# lortinchen.net
KiCad netlist of a schematic drawn in EAGLE
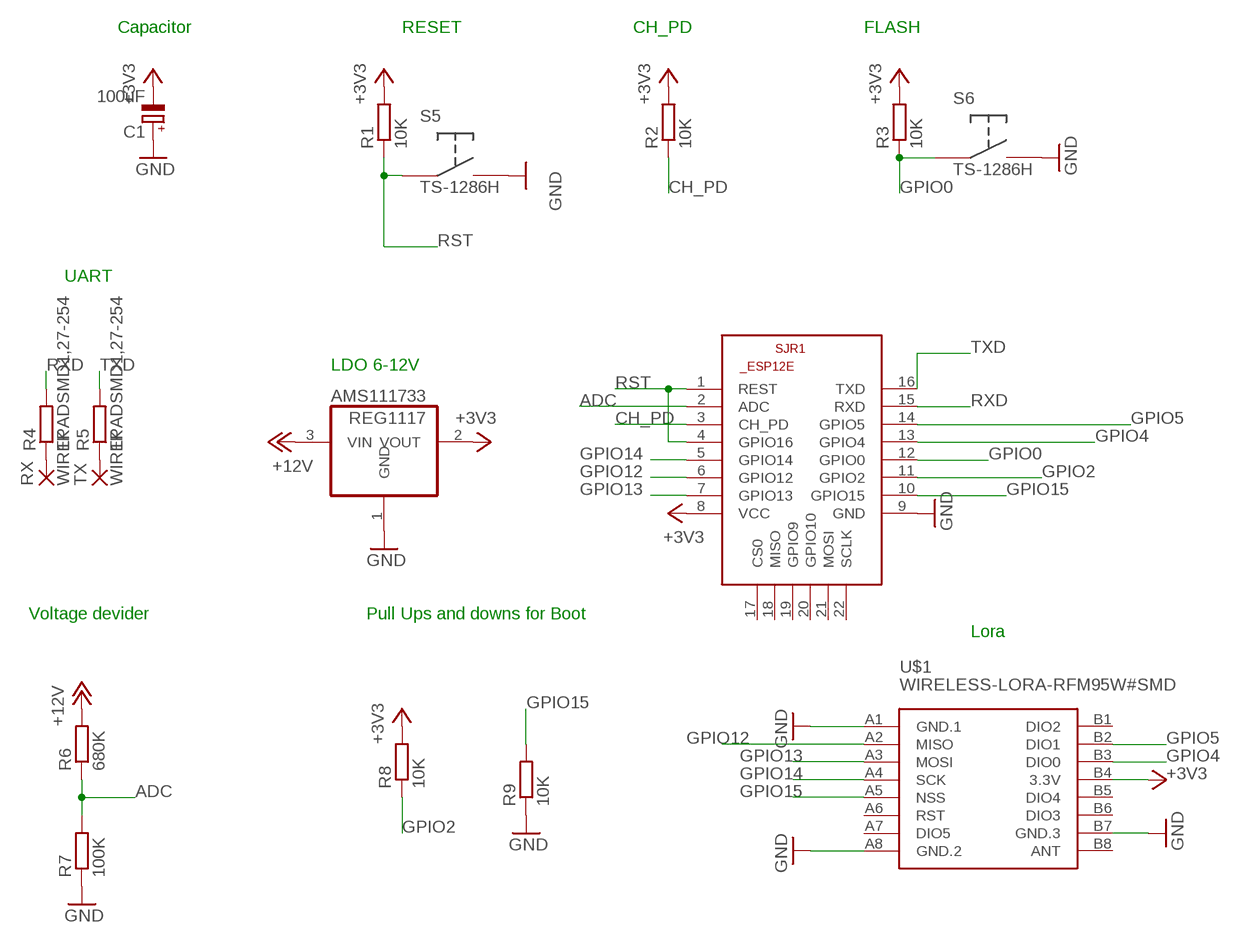
[diagram p0: schematic, sheet 1]

(export (version "E")
  (design (tool "Eeschema 10.0.6"))
  (components
    (comp (ref "AMS111733")
      (value "REG1117")
      (footprint "eagle-import:SOT223")
      (libsource (lib "eagle-import") (part "REG1117"))
    )
    (comp (ref "C1")
      (value "100uF")
      (footprint "eagle-import:C_6032-28R")
      (libsource (lib "eagle-import") (part "CPOL-EUC/6032-28R"))
    )
    (comp (ref "R1")
      (value "10K")
      (footprint "eagle-import:R0603")
      (libsource (lib "eagle-import") (part "R-EU_R0603"))
    )
    (comp (ref "R2")
      (value "10K")
      (footprint "eagle-import:R0603")
      (libsource (lib "eagle-import") (part "R-EU_R0603"))
    )
    (comp (ref "R3")
      (value "10K")
      (footprint "eagle-import:R0603")
      (libsource (lib "eagle-import") (part "R-EU_R0603"))
    )
    (comp (ref "R4")
      (value "1K")
      (footprint "eagle-import:R0603")
      (libsource (lib "eagle-import") (part "R-EU_R0603"))
    )
    (comp (ref "R5")
      (value "1K")
      (footprint "eagle-import:R0603")
      (libsource (lib "eagle-import") (part "R-EU_R0603"))
    )
    (comp (ref "R6")
      (value "680K")
      (footprint "eagle-import:R0603")
      (libsource (lib "eagle-import") (part "R-EU_R0603"))
    )
    (comp (ref "R7")
      (value "100K")
      (footprint "eagle-import:R0603")
      (libsource (lib "eagle-import") (part "R-EU_R0603"))
    )
    (comp (ref "R8")
      (value "10K")
      (footprint "eagle-import:R0603")
      (libsource (lib "eagle-import") (part "R-EU_R0603"))
    )
    (comp (ref "R9")
      (value "10K")
      (footprint "eagle-import:R0603")
      (libsource (lib "eagle-import") (part "R-EU_R0603"))
    )
    (comp (ref "RX")
      (value "WIREPADSMD1,27-254")
      (footprint "eagle-import:SMD1,27-2,54")
      (libsource (lib "eagle-import") (part "WIREPADSMD1,27-254"))
    )
    (comp (ref "S5")
      (value "TS-1286H")
      (footprint "eagle-import:TS-1268H")
      (libsource (lib "eagle-import") (part "TS-1286H"))
    )
    (comp (ref "S6")
      (value "TS-1286H")
      (footprint "eagle-import:TS-1268H")
      (libsource (lib "eagle-import") (part "TS-1286H"))
    )
    (comp (ref "SJR1")
      (value "ESP8266-12EESP12E")
      (footprint "eagle-import:ESP8266-ESP12E")
      (libsource (lib "eagle-import") (part "ESP8266-12EESP12E"))
    )
    (comp (ref "TX")
      (value "WIREPADSMD1,27-254")
      (footprint "eagle-import:SMD1,27-2,54")
      (libsource (lib "eagle-import") (part "WIREPADSMD1,27-254"))
    )
    (comp (ref "U$1")
      (value "WIRELESS-LORA-RFM95W#SMD")
      (footprint "eagle-import:WIRELESS-LORA-RFM95W#SMD")
      (libsource (lib "eagle-import") (part "WIRELESS-LORA-RFM95W#SMD"))
    )
  )
  (nets
    (net (code "1") (name "+3V3") (class "Default")
      (node (ref "AMS111733") (pin "2") (pinfunction "VOUT_2") (pintype "output"))
      (node (ref "C1") (pin "-") (pinfunction "-_-") (pintype "passive"))
      (node (ref "R1") (pin "2") (pinfunction "2_2") (pintype "passive"))
      (node (ref "R2") (pin "2") (pinfunction "2_2") (pintype "passive"))
      (node (ref "R3") (pin "2") (pinfunction "2_2") (pintype "passive"))
      (node (ref "R8") (pin "2") (pinfunction "2_2") (pintype "passive"))
      (node (ref "SJR1") (pin "8") (pinfunction "VCC_8") (pintype "bidirectional"))
      (node (ref "U$1") (pin "B4") (pinfunction "3.3V_B4") (pintype "power_in"))
    )
    (net (code "2") (name "+12V") (class "Default")
      (node (ref "AMS111733") (pin "3") (pinfunction "VIN_3") (pintype "input"))
      (node (ref "R6") (pin "2") (pinfunction "2_2") (pintype "passive"))
    )
    (net (code "3") (name "/ADC") (class "Default")
      (node (ref "R6") (pin "1") (pinfunction "1_1") (pintype "passive"))
      (node (ref "R7") (pin "2") (pinfunction "2_2") (pintype "passive"))
      (node (ref "SJR1") (pin "2") (pinfunction "ADC_2") (pintype "bidirectional"))
    )
    (net (code "4") (name "/CH_PD") (class "Default")
      (node (ref "R2") (pin "1") (pinfunction "1_1") (pintype "passive"))
      (node (ref "SJR1") (pin "3") (pinfunction "CH_PD_3") (pintype "bidirectional"))
    )
    (net (code "5") (name "/GPIO0") (class "Default")
      (node (ref "R3") (pin "1") (pinfunction "1_1") (pintype "passive"))
      (node (ref "S6") (pin "P$1") (pinfunction "P$1_P$1") (pintype "bidirectional"))
      (node (ref "SJR1") (pin "12") (pinfunction "GPIO0_12") (pintype "bidirectional"))
    )
    (net (code "6") (name "/GPIO2") (class "Default")
      (node (ref "R8") (pin "1") (pinfunction "1_1") (pintype "passive"))
      (node (ref "SJR1") (pin "11") (pinfunction "GPIO2_11") (pintype "bidirectional"))
    )
    (net (code "7") (name "/GPIO4") (class "Default")
      (node (ref "SJR1") (pin "13") (pinfunction "GPIO4_13") (pintype "bidirectional"))
      (node (ref "U$1") (pin "B3") (pinfunction "DIO0_B3") (pintype "bidirectional"))
    )
    (net (code "8") (name "/GPIO5") (class "Default")
      (node (ref "SJR1") (pin "14") (pinfunction "GPIO5_14") (pintype "bidirectional"))
      (node (ref "U$1") (pin "B2") (pinfunction "DIO1_B2") (pintype "bidirectional"))
    )
    (net (code "9") (name "/GPIO12") (class "Default")
      (node (ref "SJR1") (pin "6") (pinfunction "GPIO12_6") (pintype "bidirectional"))
      (node (ref "U$1") (pin "A2") (pinfunction "MISO_A2") (pintype "bidirectional"))
    )
    (net (code "10") (name "/GPIO13") (class "Default")
      (node (ref "SJR1") (pin "7") (pinfunction "GPIO13_7") (pintype "bidirectional"))
      (node (ref "U$1") (pin "A3") (pinfunction "MOSI_A3") (pintype "bidirectional"))
    )
    (net (code "11") (name "/GPIO14") (class "Default")
      (node (ref "SJR1") (pin "5") (pinfunction "GPIO14_5") (pintype "bidirectional"))
      (node (ref "U$1") (pin "A4") (pinfunction "SCK_A4") (pintype "bidirectional"))
    )
    (net (code "12") (name "/GPIO15") (class "Default")
      (node (ref "R9") (pin "2") (pinfunction "2_2") (pintype "passive"))
      (node (ref "SJR1") (pin "10") (pinfunction "GPIO15_10") (pintype "bidirectional"))
      (node (ref "U$1") (pin "A5") (pinfunction "NSS_A5") (pintype "bidirectional"))
    )
    (net (code "13") (name "/RST") (class "Default")
      (node (ref "R1") (pin "1") (pinfunction "1_1") (pintype "passive"))
      (node (ref "S5") (pin "P$1") (pinfunction "P$1_P$1") (pintype "bidirectional"))
      (node (ref "SJR1") (pin "1") (pinfunction "REST_1") (pintype "bidirectional"))
      (node (ref "SJR1") (pin "4") (pinfunction "GPIO16_4") (pintype "bidirectional"))
    )
    (net (code "14") (name "/RXD") (class "Default")
      (node (ref "R4") (pin "2") (pinfunction "2_2") (pintype "passive"))
      (node (ref "SJR1") (pin "15") (pinfunction "RXD_15") (pintype "bidirectional"))
    )
    (net (code "15") (name "/TXD") (class "Default")
      (node (ref "R5") (pin "2") (pinfunction "2_2") (pintype "passive"))
      (node (ref "SJR1") (pin "16") (pinfunction "TXD_16") (pintype "bidirectional"))
    )
    (net (code "16") (name "GND") (class "Default")
      (node (ref "AMS111733") (pin "1") (pinfunction "GND_1") (pintype "power_in"))
      (node (ref "C1") (pin "+") (pinfunction "+_+") (pintype "passive"))
      (node (ref "R7") (pin "1") (pinfunction "1_1") (pintype "passive"))
      (node (ref "R9") (pin "1") (pinfunction "1_1") (pintype "passive"))
      (node (ref "S5") (pin "P$2") (pinfunction "P$2_P$2") (pintype "bidirectional"))
      (node (ref "S6") (pin "P$2") (pinfunction "P$2_P$2") (pintype "bidirectional"))
      (node (ref "SJR1") (pin "9") (pinfunction "GND_9") (pintype "bidirectional"))
      (node (ref "U$1") (pin "A1") (pinfunction "GND.1_A1") (pintype "power_in"))
      (node (ref "U$1") (pin "A8") (pinfunction "GND.2_A8") (pintype "power_in"))
      (node (ref "U$1") (pin "B7") (pinfunction "GND.3_B7") (pintype "power_in"))
    )
    (net (code "17") (name "Net-(RX-P)") (class "Default")
      (node (ref "R4") (pin "1") (pinfunction "1_1") (pintype "passive"))
      (node (ref "RX") (pin "1") (pinfunction "P_1") (pintype "passive"))
    )
    (net (code "18") (name "Net-(TX-P)") (class "Default")
      (node (ref "R5") (pin "1") (pinfunction "1_1") (pintype "passive"))
      (node (ref "TX") (pin "1") (pinfunction "P_1") (pintype "passive"))
    )
    (net (code "19") (name "unconnected-(SJR1-CS0-Pad17)") (class "Default")
      (node (ref "SJR1") (pin "17") (pinfunction "CS0_17") (pintype "bidirectional"))
    )
    (net (code "20") (name "unconnected-(SJR1-GPIO9-Pad19)") (class "Default")
      (node (ref "SJR1") (pin "19") (pinfunction "GPIO9_19") (pintype "bidirectional"))
    )
    (net (code "21") (name "unconnected-(SJR1-GPIO10-Pad20)") (class "Default")
      (node (ref "SJR1") (pin "20") (pinfunction "GPIO10_20") (pintype "bidirectional"))
    )
    (net (code "22") (name "unconnected-(SJR1-MISO-Pad18)") (class "Default")
      (node (ref "SJR1") (pin "18") (pinfunction "MISO_18") (pintype "bidirectional"))
    )
    (net (code "23") (name "unconnected-(SJR1-MOSI-Pad21)") (class "Default")
      (node (ref "SJR1") (pin "21") (pinfunction "MOSI_21") (pintype "bidirectional"))
    )
    (net (code "24") (name "unconnected-(SJR1-SCLK-Pad22)") (class "Default")
      (node (ref "SJR1") (pin "22") (pinfunction "SCLK_22") (pintype "bidirectional"))
    )
    (net (code "25") (name "unconnected-(U$1-ANT-PadB8)") (class "Default")
      (node (ref "U$1") (pin "B8") (pinfunction "ANT_B8") (pintype "passive"))
    )
    (net (code "26") (name "unconnected-(U$1-DIO2-PadB1)") (class "Default")
      (node (ref "U$1") (pin "B1") (pinfunction "DIO2_B1") (pintype "bidirectional"))
    )
    (net (code "27") (name "unconnected-(U$1-DIO3-PadB6)") (class "Default")
      (node (ref "U$1") (pin "B6") (pinfunction "DIO3_B6") (pintype "bidirectional"))
    )
    (net (code "28") (name "unconnected-(U$1-DIO4-PadB5)") (class "Default")
      (node (ref "U$1") (pin "B5") (pinfunction "DIO4_B5") (pintype "bidirectional"))
    )
    (net (code "29") (name "unconnected-(U$1-DIO5-PadA7)") (class "Default")
      (node (ref "U$1") (pin "A7") (pinfunction "DIO5_A7") (pintype "bidirectional"))
    )
    (net (code "30") (name "unconnected-(U$1-RST-PadA6)") (class "Default")
      (node (ref "U$1") (pin "A6") (pinfunction "RST_A6") (pintype "bidirectional"))
    )
  )
)
